# EZPDK8SCH_easyeda.net
KiCad netlist of a schematic drawn in EasyEDA
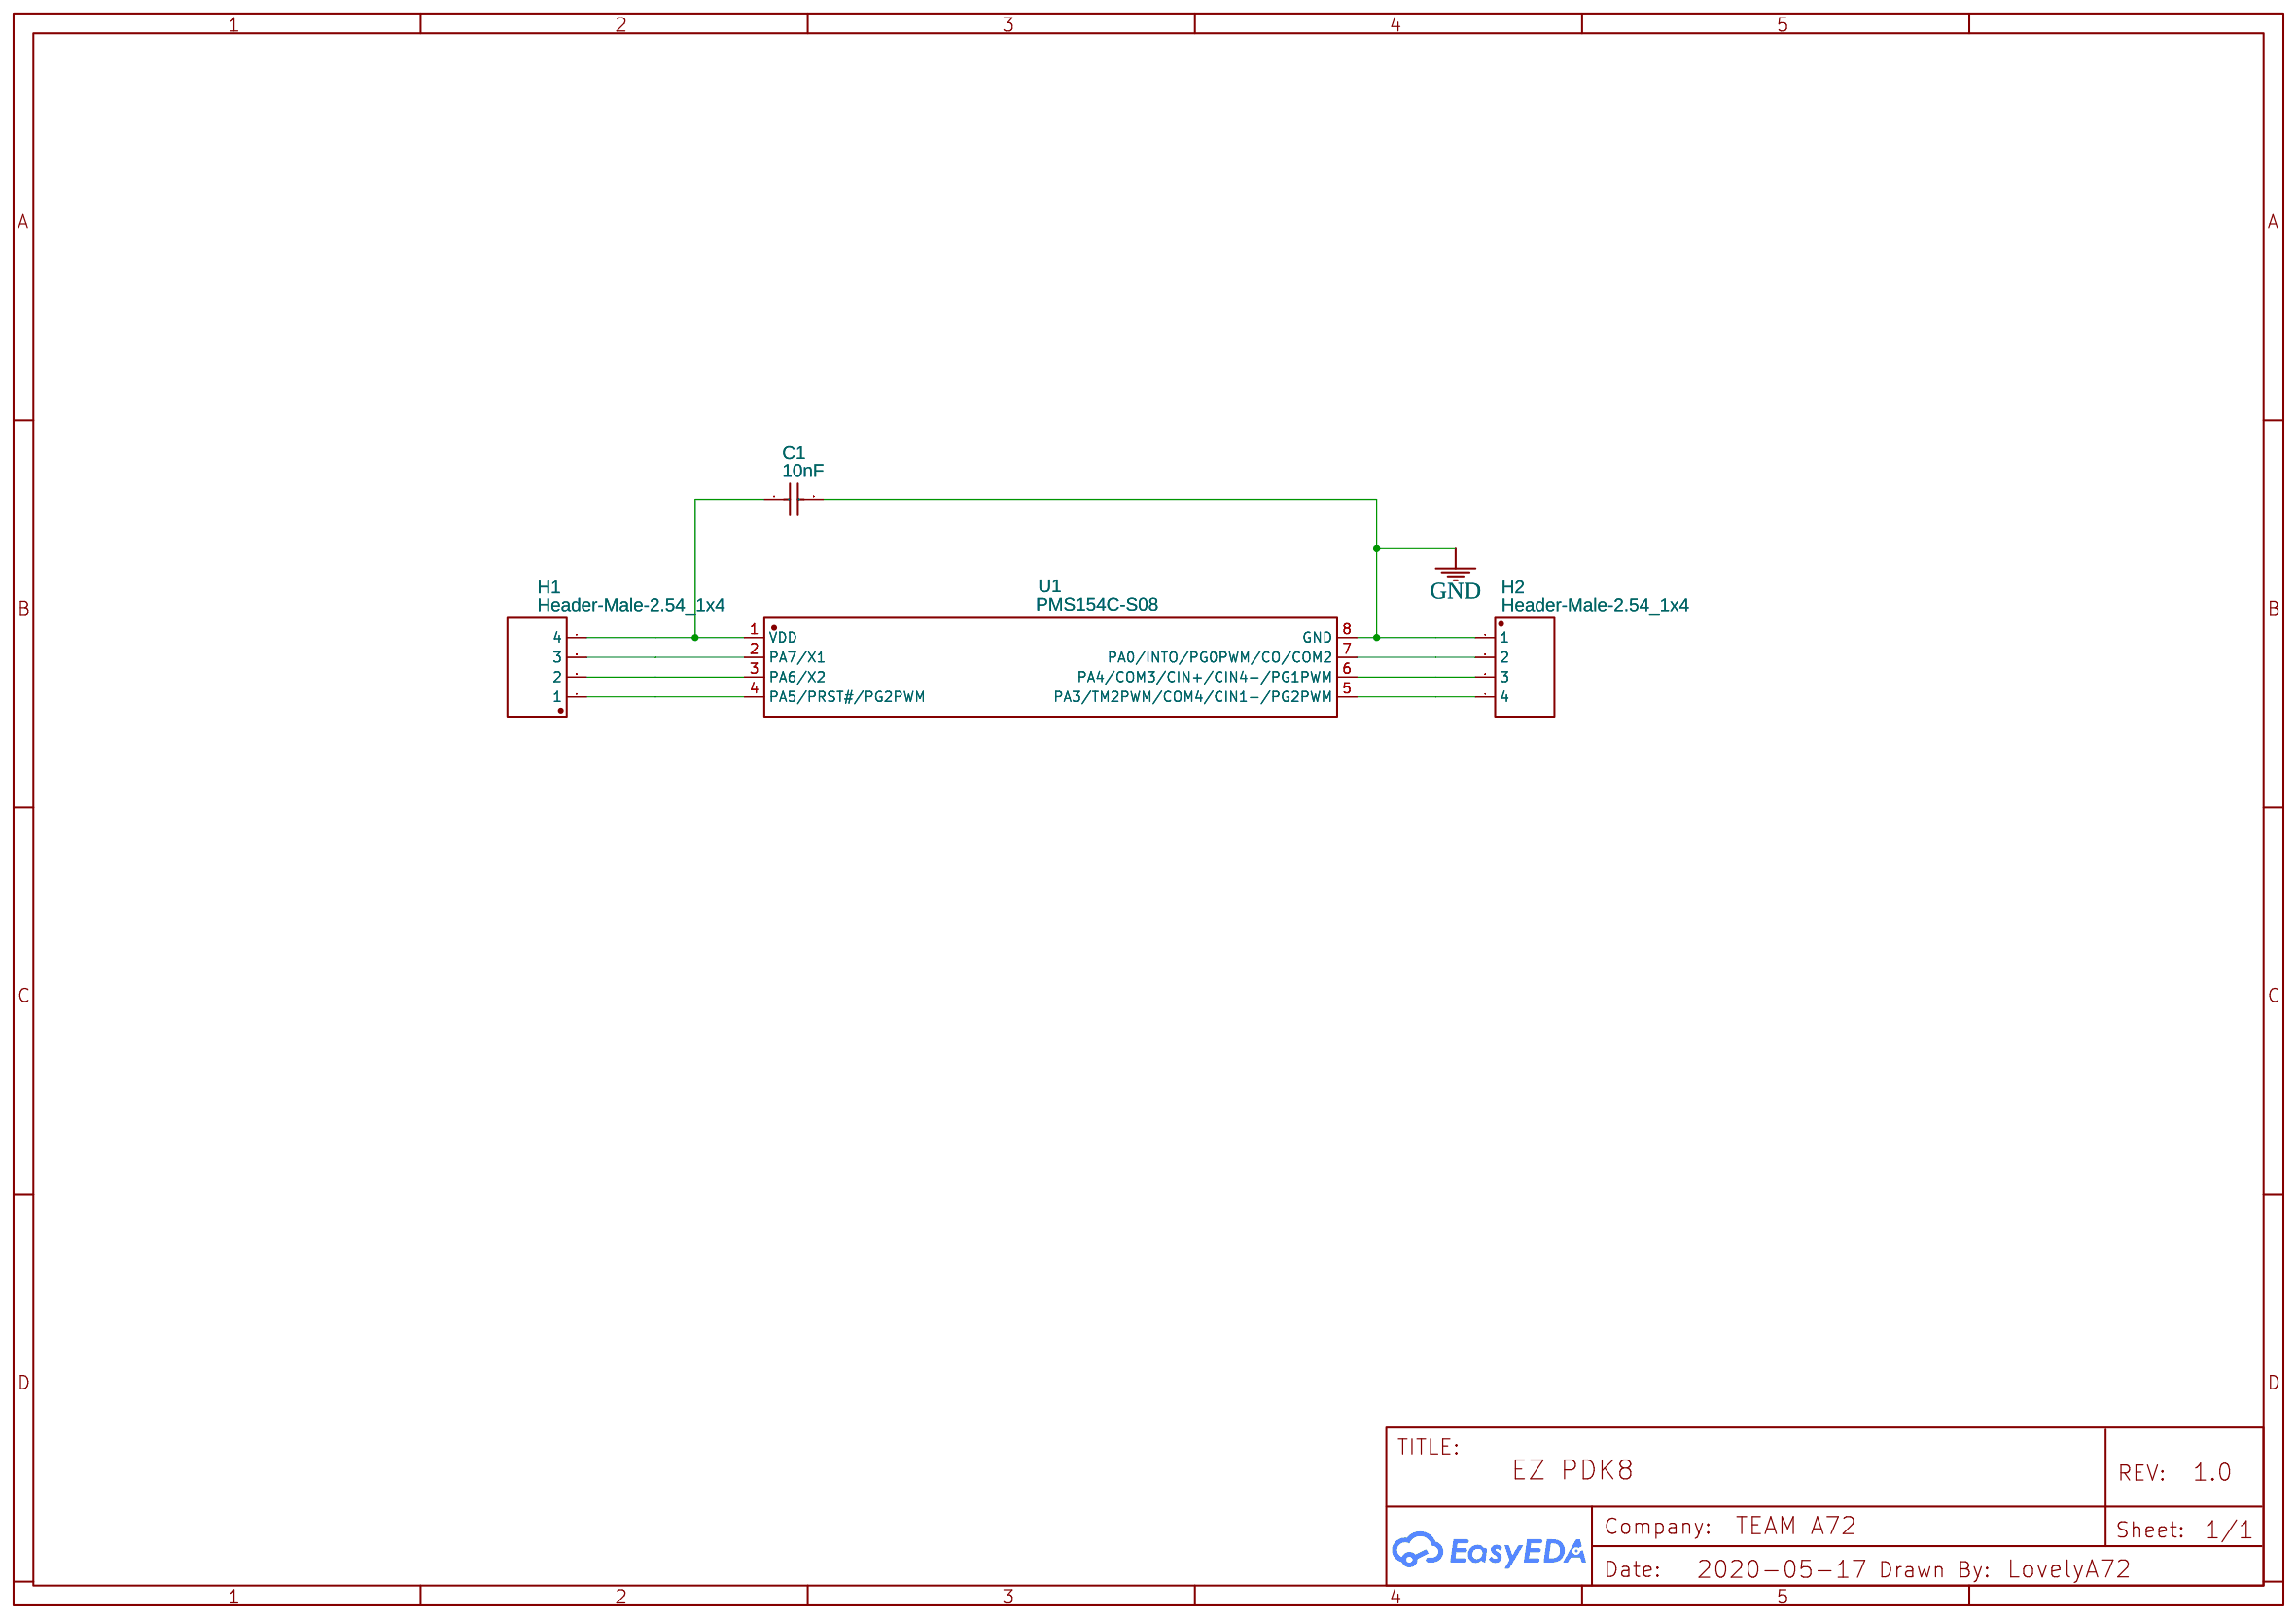
[diagram p0: schematic sheet]

(export (version "E")
  (design (tool "Eeschema 10.0.6"))
  (components
    (comp (ref "C1")
      (value "10nF")
      (fields
        (field (name "BOM_Manufacturer Part") "0805CG103J500NT")
        (field (name "BOM_Supplier Part") "C63849")
      )
      (libsource (lib "") (part "0805CG103J500NT"))
    )
    (comp (ref "H1")
      (value "Header-Male-2.54_1x4")
      (fields
        (field (name "BOM_Manufacturer Part") "210S-1*4P L=11.6MMGold-plated black")
        (field (name "BOM_Supplier Part") "C124378")
      )
      (libsource (lib "") (part "Header-Male-2.54_1x4_1"))
    )
    (comp (ref "H2")
      (value "Header-Male-2.54_1x4")
      (fields
        (field (name "BOM_Manufacturer Part") "210S-1*4P L=11.6MMGold-plated black")
        (field (name "BOM_Supplier Part") "C124378")
      )
      (libsource (lib "") (part "Header-Male-2.54_1x4"))
    )
    (comp (ref "U1")
      (value "PMS154C-S08")
      (fields (field (name "BOM_Supplier Part") "C168657"))
      (libsource (lib "") (part "PMS154C-S08"))
    )
  )
  (nets
    (net (code "1") (name "GND") (class "Default")
      (node (ref "C1") (pin "2") (pinfunction "2_2") (pintype "input"))
      (node (ref "H2") (pin "1") (pinfunction "1_1") (pintype "unspecified"))
      (node (ref "U1") (pin "8") (pinfunction "GND_8") (pintype "unspecified"))
    )
    (net (code "2") (name "Net-(U1-PA0{slash}INTO{slash}PG0PWM{slash}CO{slash}COM2)") (class "Default")
      (node (ref "H2") (pin "2") (pinfunction "2_2") (pintype "unspecified"))
      (node (ref "U1") (pin "7") (pinfunction "PA0/INTO/PG0PWM/CO/COM2_7") (pintype "unspecified"))
    )
    (net (code "3") (name "Net-(U1-PA3{slash}TM2PWM{slash}COM4{slash}CIN1-{slash}PG2PWM)") (class "Default")
      (node (ref "H2") (pin "4") (pinfunction "4_4") (pintype "unspecified"))
      (node (ref "U1") (pin "5") (pinfunction "PA3/TM2PWM/COM4/CIN1-/PG2PWM_5") (pintype "unspecified"))
    )
    (net (code "4") (name "Net-(U1-PA4{slash}COM3{slash}CIN+{slash}CIN4-{slash}PG1PWM)") (class "Default")
      (node (ref "H2") (pin "3") (pinfunction "3_3") (pintype "unspecified"))
      (node (ref "U1") (pin "6") (pinfunction "PA4/COM3/CIN+/CIN4-/PG1PWM_6") (pintype "unspecified"))
    )
    (net (code "5") (name "Net-(U1-PA5{slash}PRST#{slash}PG2PWM)") (class "Default")
      (node (ref "H1") (pin "1") (pinfunction "1_1") (pintype "unspecified"))
      (node (ref "U1") (pin "4") (pinfunction "PA5/PRST#/PG2PWM_4") (pintype "unspecified"))
    )
    (net (code "6") (name "Net-(U1-PA6{slash}X2)") (class "Default")
      (node (ref "H1") (pin "2") (pinfunction "2_2") (pintype "unspecified"))
      (node (ref "U1") (pin "3") (pinfunction "PA6/X2_3") (pintype "unspecified"))
    )
    (net (code "7") (name "Net-(U1-PA7{slash}X1)") (class "Default")
      (node (ref "H1") (pin "3") (pinfunction "3_3") (pintype "unspecified"))
      (node (ref "U1") (pin "2") (pinfunction "PA7/X1_2") (pintype "unspecified"))
    )
    (net (code "8") (name "Net-(U1-VDD)") (class "Default")
      (node (ref "C1") (pin "1") (pinfunction "1_1") (pintype "input"))
      (node (ref "H1") (pin "4") (pinfunction "4_4") (pintype "unspecified"))
      (node (ref "U1") (pin "1") (pinfunction "VDD_1") (pintype "unspecified"))
    )
  )
)
